# PS_Filter.net
KiCad netlist of a schematic drawn in Altium Designer
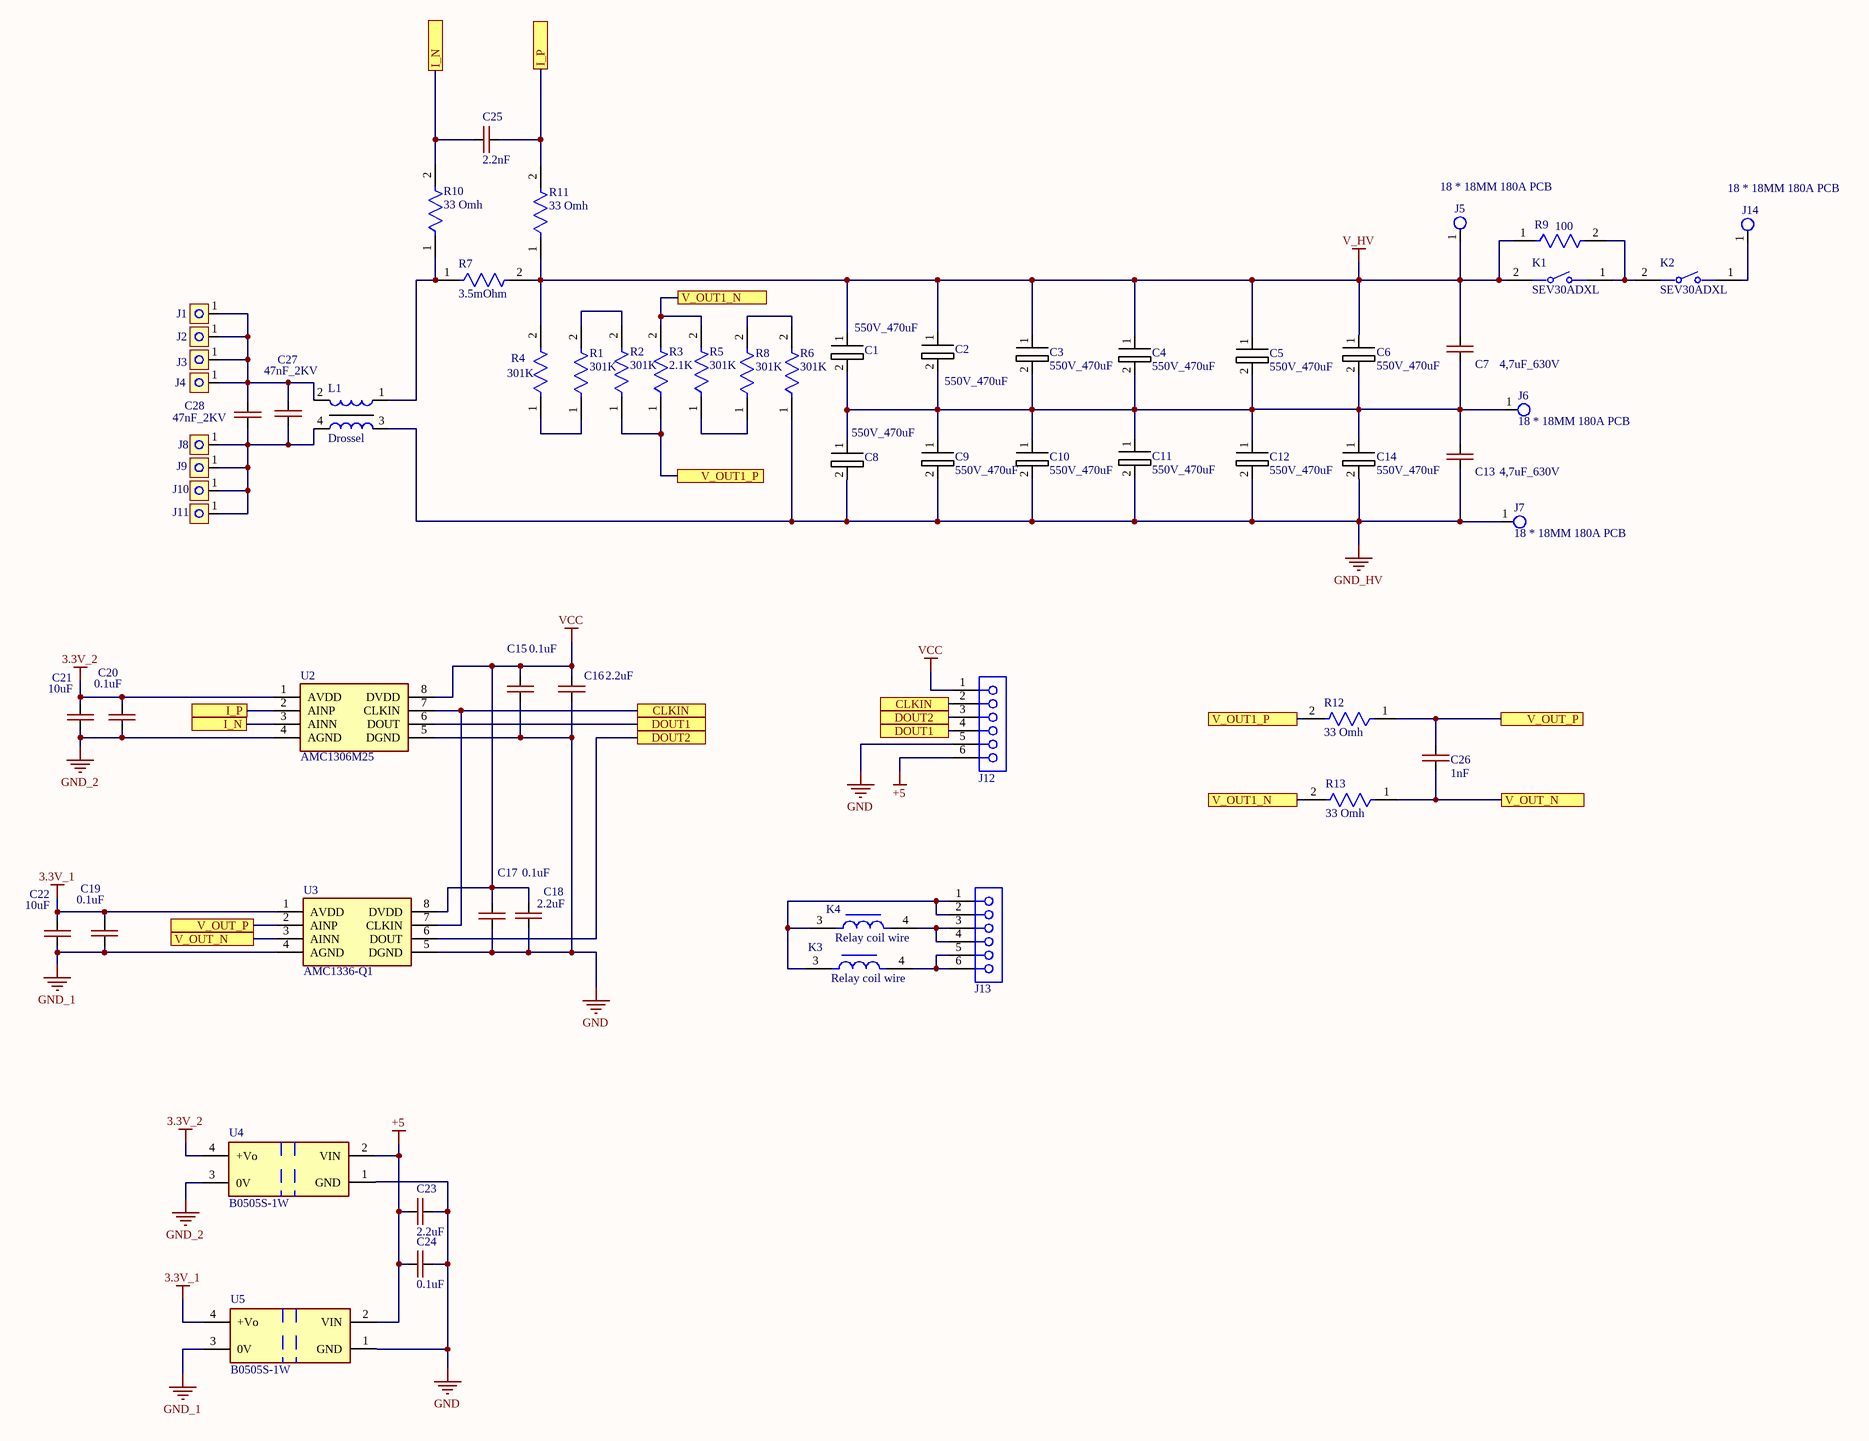
[diagram p0: PS_Filter.SchDoc]

(export (version "E")
  (design (tool "Eeschema 10.0.6"))
  (components
    (comp (ref "C1")
      (value "550V_470uF")
      (footprint "500V_470uF")
      (libsource (lib "PASSIVE_COMPONENTS") (part "CAP_POL_LOW_IMP"))
    )
    (comp (ref "C2")
      (value "550V_470uF")
      (footprint "500V_470uF")
      (libsource (lib "PASSIVE_COMPONENTS") (part "CAP_POL_LOW_IMP"))
    )
    (comp (ref "C3")
      (value "550V_470uF")
      (footprint "500V_470uF")
      (libsource (lib "PASSIVE_COMPONENTS") (part "CAP_POL_LOW_IMP"))
    )
    (comp (ref "C4")
      (value "550V_470uF")
      (footprint "500V_470uF")
      (libsource (lib "PASSIVE_COMPONENTS") (part "CAP_POL_LOW_IMP"))
    )
    (comp (ref "C5")
      (value "550V_470uF")
      (footprint "500V_470uF")
      (libsource (lib "PASSIVE_COMPONENTS") (part "CAP_POL_LOW_IMP"))
    )
    (comp (ref "C6")
      (value "550V_470uF")
      (footprint "500V_470uF")
      (libsource (lib "PASSIVE_COMPONENTS") (part "CAP_POL_LOW_IMP"))
    )
    (comp (ref "C7")
      (value "4,7uF_630V")
      (footprint "CAP_4.7uF_630V")
      (libsource (lib "PASSIVE_COMPONENTS") (part "CAP-NON-POLAR"))
    )
    (comp (ref "C8")
      (value "550V_470uF")
      (footprint "500V_470uF")
      (libsource (lib "PASSIVE_COMPONENTS") (part "CAP_POL_LOW_IMP"))
    )
    (comp (ref "C9")
      (value "550V_470uF")
      (footprint "500V_470uF")
      (libsource (lib "PASSIVE_COMPONENTS") (part "CAP_POL_LOW_IMP"))
    )
    (comp (ref "C10")
      (value "550V_470uF")
      (footprint "500V_470uF")
      (libsource (lib "PASSIVE_COMPONENTS") (part "CAP_POL_LOW_IMP"))
    )
    (comp (ref "C11")
      (value "550V_470uF")
      (footprint "500V_470uF")
      (libsource (lib "PASSIVE_COMPONENTS") (part "CAP_POL_LOW_IMP"))
    )
    (comp (ref "C12")
      (value "550V_470uF")
      (footprint "500V_470uF")
      (libsource (lib "PASSIVE_COMPONENTS") (part "CAP_POL_LOW_IMP"))
    )
    (comp (ref "C13")
      (value "4,7uF_630V")
      (footprint "CAP_4.7uF_630V")
      (libsource (lib "PASSIVE_COMPONENTS") (part "CAP-NON-POLAR"))
    )
    (comp (ref "C14")
      (value "550V_470uF")
      (footprint "500V_470uF")
      (libsource (lib "PASSIVE_COMPONENTS") (part "CAP_POL_LOW_IMP"))
    )
    (comp (ref "C15")
      (value "0.1uF")
      (footprint "CAP-0603")
      (libsource (lib "PASSIVE_COMPONENTS") (part "CAP-NON-POLAR"))
    )
    (comp (ref "C16")
      (value "2.2uF")
      (footprint "CAP-0603")
      (libsource (lib "PASSIVE_COMPONENTS") (part "CAP-NON-POLAR"))
    )
    (comp (ref "C17")
      (value "0.1uF")
      (footprint "CAP-0603")
      (libsource (lib "PASSIVE_COMPONENTS") (part "CAP-NON-POLAR"))
    )
    (comp (ref "C18")
      (value "2.2uF")
      (footprint "CAP-0603")
      (libsource (lib "PASSIVE_COMPONENTS") (part "CAP-NON-POLAR"))
    )
    (comp (ref "C19")
      (value "0.1uF")
      (footprint "CAP-0603")
      (libsource (lib "PASSIVE_COMPONENTS") (part "CAP-NON-POLAR"))
    )
    (comp (ref "C20")
      (value "0.1uF")
      (footprint "CAP-0603")
      (libsource (lib "PASSIVE_COMPONENTS") (part "CAP-NON-POLAR"))
    )
    (comp (ref "C21")
      (value "10uF")
      (footprint "CAP-0603")
      (libsource (lib "PASSIVE_COMPONENTS") (part "CAP-NON-POLAR"))
    )
    (comp (ref "C22")
      (value "10uF")
      (footprint "CAP-0603")
      (libsource (lib "PASSIVE_COMPONENTS") (part "CAP-NON-POLAR"))
    )
    (comp (ref "C23")
      (value "2.2uF")
      (footprint "CAP-0603")
      (libsource (lib "PASSIVE_COMPONENTS") (part "CAP-NON-POLAR"))
    )
    (comp (ref "C24")
      (value "0.1uF")
      (footprint "CAP-0603")
      (libsource (lib "PASSIVE_COMPONENTS") (part "CAP-NON-POLAR"))
    )
    (comp (ref "C25")
      (value "2.2nF")
      (footprint "CAP-0603")
      (libsource (lib "PASSIVE_COMPONENTS") (part "CAP-NON-POLAR"))
    )
    (comp (ref "C26")
      (value "1nF")
      (footprint "CAP-0603")
      (libsource (lib "PASSIVE_COMPONENTS") (part "CAP-NON-POLAR"))
    )
    (comp (ref "C27")
      (value "47nF_2KV")
      (footprint "47nF_2kV")
      (libsource (lib "PASSIVE_COMPONENTS") (part "CAP-V"))
    )
    (comp (ref "C28")
      (value "47nF_2KV")
      (footprint "47nF_2kV")
      (libsource (lib "PASSIVE_COMPONENTS") (part "CAP-V"))
    )
    (comp (ref "J1")
      (value "KF136HT-10.16")
      (footprint "Conn_MEIGAN_MG136HT")
      (libsource (lib "Connectors") (part "Connector_MEIGAN_MG136HT"))
    )
    (comp (ref "J2")
      (value "KF136HT-10.16")
      (footprint "Conn_MEIGAN_MG136HT")
      (libsource (lib "Connectors") (part "Connector_MEIGAN_MG136HT"))
    )
    (comp (ref "J3")
      (value "KF136HT-10.16")
      (footprint "Conn_MEIGAN_MG136HT")
      (libsource (lib "Connectors") (part "Connector_MEIGAN_MG136HT"))
    )
    (comp (ref "J4")
      (value "KF136HT-10.16")
      (footprint "Conn_MEIGAN_MG136HT")
      (libsource (lib "Connectors") (part "Connector_MEIGAN_MG136HT"))
    )
    (comp (ref "J5")
      (value "18 * 18MM 180A PCB")
      (footprint "M8 Conn")
      (description "18 * 18MM 180A PCB High Current Solder Terminal Copper Terminal Fastener M8 Nut")
      (libsource (lib "Connectors") (part "Klema_15_A"))
    )
    (comp (ref "J6")
      (value "18 * 18MM 180A PCB")
      (footprint "M8 Conn")
      (description "18 * 18MM 180A PCB High Current Solder Terminal Copper Terminal Fastener M8 Nut")
      (libsource (lib "Connectors") (part "Klema_15_A"))
    )
    (comp (ref "J7")
      (value "18 * 18MM 180A PCB")
      (footprint "M8 Conn")
      (description "18 * 18MM 180A PCB High Current Solder Terminal Copper Terminal Fastener M8 Nut")
      (libsource (lib "Connectors") (part "Klema_15_A"))
    )
    (comp (ref "J8")
      (value "KF136HT-10.16")
      (footprint "Conn_MEIGAN_MG136HT")
      (libsource (lib "Connectors") (part "Connector_MEIGAN_MG136HT"))
    )
    (comp (ref "J9")
      (value "KF136HT-10.16")
      (footprint "Conn_MEIGAN_MG136HT")
      (libsource (lib "Connectors") (part "Connector_MEIGAN_MG136HT"))
    )
    (comp (ref "J10")
      (value "KF136HT-10.16")
      (footprint "Conn_MEIGAN_MG136HT")
      (libsource (lib "Connectors") (part "Connector_MEIGAN_MG136HT"))
    )
    (comp (ref "J11")
      (value "KF136HT-10.16")
      (footprint "Conn_MEIGAN_MG136HT")
      (libsource (lib "Connectors") (part "Connector_MEIGAN_MG136HT"))
    )
    (comp (ref "J12")
      (value "61300611821")
      (footprint "61300611821")
      (description "WR-PHD Socket Header, THT, Vertical, pitch 2.54mm, 1 Row, 6P")
      (fields (field (name "MANUFACTURER") "Wurth Elektronik"))
      (libsource (lib "Altium_WR-PHD (rev24a)") (part "61300611821"))
    )
    (comp (ref "J13")
      (value "61300611821")
      (footprint "61300611821")
      (description "WR-PHD Socket Header, THT, Vertical, pitch 2.54mm, 1 Row, 6P")
      (fields (field (name "MANUFACTURER") "Wurth Elektronik"))
      (libsource (lib "Altium_WR-PHD (rev24a)") (part "61300611821"))
    )
    (comp (ref "J14")
      (value "18 * 18MM 180A PCB")
      (footprint "M8 Conn")
      (description "18 * 18MM 180A PCB High Current Solder Terminal Copper Terminal Fastener M8 Nut")
      (libsource (lib "Connectors") (part "Klema_15_A"))
    )
    (comp (ref "K1")
      (value "SEV30ADXL")
      (footprint "Relay_1000VDC_30A")
      (description "5-1000V 30A DC Contactor Power Relay SEV30ADXL Coil 12V")
      (libsource (lib "Relays") (part "Relay"))
    )
    (comp (ref "K2")
      (value "SEV30ADXL")
      (footprint "Relay_1000VDC_30A")
      (description "5-1000V 30A DC Contactor Power Relay SEV30ADXL Coil 12V")
      (libsource (lib "Relays") (part "Relay"))
    )
    (comp (ref "K3")
      (value "Relay coil wire")
      (footprint "Relay_Coil")
      (libsource (lib "Relays") (part "Coil_relay"))
    )
    (comp (ref "K4")
      (value "Relay coil wire")
      (footprint "Relay_Coil")
      (libsource (lib "Relays") (part "Coil_relay"))
    )
    (comp (ref "L1")
      (value "Drossel")
      (footprint "T47x27x15")
      (libsource (lib "Transformers") (part "Drossel_Synphaze"))
    )
    (comp (ref "R1")
      (value "301K")
      (footprint "RES-2512")
      (description "301K   0.1%")
      (libsource (lib "PASSIVE_COMPONENTS") (part "RES-CONST"))
    )
    (comp (ref "R2")
      (value "301K")
      (footprint "RES-2512")
      (description "301K   0.1%")
      (libsource (lib "PASSIVE_COMPONENTS") (part "RES-CONST"))
    )
    (comp (ref "R3")
      (value "2.1K")
      (footprint "RES-2512")
      (description "2.1K   0.1%")
      (libsource (lib "PASSIVE_COMPONENTS") (part "RES-CONST"))
    )
    (comp (ref "R4")
      (value "301K")
      (footprint "RES-2512")
      (description "301K   0.1%")
      (libsource (lib "PASSIVE_COMPONENTS") (part "RES-CONST"))
    )
    (comp (ref "R5")
      (value "301K")
      (footprint "RES-2512")
      (description "301K   0.1%")
      (libsource (lib "PASSIVE_COMPONENTS") (part "RES-CONST"))
    )
    (comp (ref "R6")
      (value "301K")
      (footprint "RES-2512")
      (description "301K   0.1%")
      (libsource (lib "PASSIVE_COMPONENTS") (part "RES-CONST"))
    )
    (comp (ref "R7")
      (value "3.5mOhm")
      (footprint "RES-3921")
      (description "3.5mOhm 1%  3920")
      (libsource (lib "PASSIVE_COMPONENTS") (part "RES-CONST"))
    )
    (comp (ref "R8")
      (value "301K")
      (footprint "RES-2512")
      (description "301K   0.1%")
      (libsource (lib "PASSIVE_COMPONENTS") (part "RES-CONST"))
    )
    (comp (ref "R9")
      (value "100")
      (footprint "RES_100W_Aluminium")
      (description "100W RX24 Aluminum Power Metal Shell Case Wirewound Resistor 100Omh")
      (libsource (lib "PASSIVE_COMPONENTS") (part "RES-CONST"))
    )
    (comp (ref "R10")
      (value "33 Omh")
      (footprint "RES-0603")
      (libsource (lib "PASSIVE_COMPONENTS") (part "RES-CONST"))
    )
    (comp (ref "R11")
      (value "33 Omh")
      (footprint "RES-0603")
      (libsource (lib "PASSIVE_COMPONENTS") (part "RES-CONST"))
    )
    (comp (ref "R12")
      (value "33 Omh")
      (footprint "RES-0603")
      (libsource (lib "PASSIVE_COMPONENTS") (part "RES-CONST"))
    )
    (comp (ref "R13")
      (value "33 Omh")
      (footprint "RES-0603")
      (libsource (lib "PASSIVE_COMPONENTS") (part "RES-CONST"))
    )
    (comp (ref "U2")
      (value "AMC1306M25")
      (footprint "FP-DWV0008A-MFG")
      (libsource (lib "Integrated_Circuts") (part "AMC1306M25"))
    )
    (comp (ref "U3")
      (value "AMC1336-Q1")
      (footprint "FP-DWV0008A-MFG")
      (libsource (lib "Integrated_Circuts") (part "AMC1336"))
    )
    (comp (ref "U4")
      (value "B0505S-1W")
      (footprint "B0505S-1W")
      (libsource (lib "Integrated_Circuts") (part "B0505S-1W"))
    )
    (comp (ref "U5")
      (value "B0505S-1W")
      (footprint "B0505S-1W")
      (libsource (lib "Integrated_Circuts") (part "B0505S-1W"))
    )
  )
  (nets
    (net (code "1") (name "+5") (class "Default")
      (node (ref "C23") (pin "1") (pinfunction "1_1") (pintype "passive"))
      (node (ref "C24") (pin "1") (pinfunction "1_1") (pintype "passive"))
      (node (ref "J12") (pin "6") (pinfunction "6_6") (pintype "passive"))
      (node (ref "U4") (pin "2") (pinfunction "VIN_2") (pintype "power_in"))
      (node (ref "U5") (pin "2") (pinfunction "VIN_2") (pintype "power_in"))
    )
    (net (code "2") (name "/CLKIN") (class "Default")
      (node (ref "J12") (pin "2") (pinfunction "2_2") (pintype "passive"))
      (node (ref "U2") (pin "7") (pinfunction "CLKIN_7") (pintype "passive"))
      (node (ref "U3") (pin "7") (pinfunction "CLKIN_7") (pintype "passive"))
    )
    (net (code "3") (name "/DOUT1") (class "Default")
      (node (ref "J12") (pin "4") (pinfunction "4_4") (pintype "passive"))
      (node (ref "U2") (pin "6") (pinfunction "DOUT_6") (pintype "passive"))
    )
    (net (code "4") (name "/DOUT2") (class "Default")
      (node (ref "J12") (pin "3") (pinfunction "3_3") (pintype "passive"))
      (node (ref "U3") (pin "6") (pinfunction "DOUT_6") (pintype "passive"))
    )
    (net (code "5") (name "/I_N") (class "Default")
      (node (ref "C25") (pin "1") (pinfunction "1_1") (pintype "passive"))
      (node (ref "R10") (pin "2") (pinfunction "2_2") (pintype "passive"))
      (node (ref "U2") (pin "3") (pinfunction "AINN_3") (pintype "passive"))
    )
    (net (code "6") (name "/I_P") (class "Default")
      (node (ref "C25") (pin "2") (pinfunction "2_2") (pintype "passive"))
      (node (ref "R11") (pin "2") (pinfunction "2_2") (pintype "passive"))
      (node (ref "U2") (pin "2") (pinfunction "AINP_2") (pintype "passive"))
    )
    (net (code "7") (name "/V_OUT1_N") (class "Default")
      (node (ref "R13") (pin "2") (pinfunction "2_2") (pintype "passive"))
      (node (ref "R3") (pin "2") (pinfunction "2_2") (pintype "passive"))
      (node (ref "R5") (pin "2") (pinfunction "2_2") (pintype "passive"))
    )
    (net (code "8") (name "/V_OUT1_P") (class "Default")
      (node (ref "R12") (pin "2") (pinfunction "2_2") (pintype "passive"))
      (node (ref "R2") (pin "1") (pinfunction "1_1") (pintype "passive"))
      (node (ref "R3") (pin "1") (pinfunction "1_1") (pintype "passive"))
    )
    (net (code "9") (name "/V_OUT_N") (class "Default")
      (node (ref "C26") (pin "2") (pinfunction "2_2") (pintype "passive"))
      (node (ref "R13") (pin "1") (pinfunction "1_1") (pintype "passive"))
      (node (ref "U3") (pin "3") (pinfunction "AINN_3") (pintype "passive"))
    )
    (net (code "10") (name "/V_OUT_P") (class "Default")
      (node (ref "C26") (pin "1") (pinfunction "1_1") (pintype "passive"))
      (node (ref "R12") (pin "1") (pinfunction "1_1") (pintype "passive"))
      (node (ref "U3") (pin "2") (pinfunction "AINP_2") (pintype "passive"))
    )
    (net (code "11") (name "3.3V_1") (class "Default")
      (node (ref "C19") (pin "1") (pinfunction "1_1") (pintype "passive"))
      (node (ref "C22") (pin "1") (pinfunction "1_1") (pintype "passive"))
      (node (ref "U3") (pin "1") (pinfunction "AVDD_1") (pintype "passive"))
      (node (ref "U5") (pin "4") (pinfunction "+Vo_4") (pintype "power_in"))
    )
    (net (code "12") (name "3.3V_2") (class "Default")
      (node (ref "C20") (pin "1") (pinfunction "1_1") (pintype "passive"))
      (node (ref "C21") (pin "1") (pinfunction "1_1") (pintype "passive"))
      (node (ref "U2") (pin "1") (pinfunction "AVDD_1") (pintype "passive"))
      (node (ref "U4") (pin "4") (pinfunction "+Vo_4") (pintype "power_in"))
    )
    (net (code "13") (name "GND") (class "Default")
      (node (ref "C15") (pin "2") (pinfunction "2_2") (pintype "passive"))
      (node (ref "C16") (pin "2") (pinfunction "2_2") (pintype "passive"))
      (node (ref "C17") (pin "2") (pinfunction "2_2") (pintype "passive"))
      (node (ref "C18") (pin "2") (pinfunction "2_2") (pintype "passive"))
      (node (ref "C23") (pin "2") (pinfunction "2_2") (pintype "passive"))
      (node (ref "C24") (pin "2") (pinfunction "2_2") (pintype "passive"))
      (node (ref "J12") (pin "5") (pinfunction "5_5") (pintype "passive"))
      (node (ref "U2") (pin "5") (pinfunction "DGND_5") (pintype "passive"))
      (node (ref "U3") (pin "5") (pinfunction "DGND_5") (pintype "passive"))
      (node (ref "U4") (pin "1") (pinfunction "GND_1") (pintype "power_in"))
      (node (ref "U5") (pin "1") (pinfunction "GND_1") (pintype "power_in"))
    )
    (net (code "14") (name "GND_1") (class "Default")
      (node (ref "C19") (pin "2") (pinfunction "2_2") (pintype "passive"))
      (node (ref "C22") (pin "2") (pinfunction "2_2") (pintype "passive"))
      (node (ref "U3") (pin "4") (pinfunction "AGND_4") (pintype "passive"))
      (node (ref "U5") (pin "3") (pinfunction "0V_3") (pintype "power_in"))
    )
    (net (code "15") (name "GND_2") (class "Default")
      (node (ref "C20") (pin "2") (pinfunction "2_2") (pintype "passive"))
      (node (ref "C21") (pin "2") (pinfunction "2_2") (pintype "passive"))
      (node (ref "U2") (pin "4") (pinfunction "AGND_4") (pintype "passive"))
      (node (ref "U4") (pin "3") (pinfunction "0V_3") (pintype "power_in"))
    )
    (net (code "16") (name "GND_HV") (class "Default")
      (node (ref "C10") (pin "2") (pinfunction "2_2") (pintype "passive"))
      (node (ref "C11") (pin "2") (pinfunction "2_2") (pintype "passive"))
      (node (ref "C12") (pin "2") (pinfunction "2_2") (pintype "passive"))
      (node (ref "C13") (pin "1") (pinfunction "1_1") (pintype "passive"))
      (node (ref "C14") (pin "2") (pinfunction "2_2") (pintype "passive"))
      (node (ref "C8") (pin "2") (pinfunction "2_2") (pintype "passive"))
      (node (ref "C9") (pin "2") (pinfunction "2_2") (pintype "passive"))
      (node (ref "J7") (pin "1") (pinfunction "0_1") (pintype "passive"))
      (node (ref "L1") (pin "3") (pinfunction "3_3") (pintype "passive"))
      (node (ref "R6") (pin "1") (pinfunction "1_1") (pintype "passive"))
    )
    (net (code "17") (name "Net-(J1-17)") (class "Default")
      (node (ref "C27") (pin "2") (pinfunction "2_2") (pintype "passive"))
      (node (ref "C28") (pin "2") (pinfunction "2_2") (pintype "passive"))
      (node (ref "J1") (pin "1") (pinfunction "17_1") (pintype "passive"))
      (node (ref "J2") (pin "1") (pinfunction "17_1") (pintype "passive"))
      (node (ref "J3") (pin "1") (pinfunction "17_1") (pintype "passive"))
      (node (ref "J4") (pin "1") (pinfunction "17_1") (pintype "passive"))
      (node (ref "L1") (pin "2") (pinfunction "2_2") (pintype "passive"))
    )
    (net (code "18") (name "Net-(J6-0)") (class "Default")
      (node (ref "C1") (pin "2") (pinfunction "2_2") (pintype "passive"))
      (node (ref "C10") (pin "1") (pinfunction "1_1") (pintype "passive"))
      (node (ref "C11") (pin "1") (pinfunction "1_1") (pintype "passive"))
      (node (ref "C12") (pin "1") (pinfunction "1_1") (pintype "passive"))
      (node (ref "C13") (pin "2") (pinfunction "2_2") (pintype "passive"))
      (node (ref "C14") (pin "1") (pinfunction "1_1") (pintype "passive"))
      (node (ref "C2") (pin "2") (pinfunction "2_2") (pintype "passive"))
      (node (ref "C3") (pin "2") (pinfunction "2_2") (pintype "passive"))
      (node (ref "C4") (pin "2") (pinfunction "2_2") (pintype "passive"))
      (node (ref "C5") (pin "2") (pinfunction "2_2") (pintype "passive"))
      (node (ref "C6") (pin "2") (pinfunction "2_2") (pintype "passive"))
      (node (ref "C7") (pin "1") (pinfunction "1_1") (pintype "passive"))
      (node (ref "C8") (pin "1") (pinfunction "1_1") (pintype "passive"))
      (node (ref "C9") (pin "1") (pinfunction "1_1") (pintype "passive"))
      (node (ref "J6") (pin "1") (pinfunction "0_1") (pintype "passive"))
    )
    (net (code "19") (name "Net-(J10-17)") (class "Default")
      (node (ref "C27") (pin "1") (pinfunction "1_1") (pintype "passive"))
      (node (ref "C28") (pin "1") (pinfunction "1_1") (pintype "passive"))
      (node (ref "J10") (pin "1") (pinfunction "17_1") (pintype "passive"))
      (node (ref "J11") (pin "1") (pinfunction "17_1") (pintype "passive"))
      (node (ref "J8") (pin "1") (pinfunction "17_1") (pintype "passive"))
      (node (ref "J9") (pin "1") (pinfunction "17_1") (pintype "passive"))
      (node (ref "L1") (pin "4") (pinfunction "4_4") (pintype "passive"))
    )
    (net (code "20") (name "Net-(J13-Pad1)") (class "Default")
      (node (ref "J13") (pin "1") (pinfunction "1_1") (pintype "passive"))
      (node (ref "J13") (pin "2") (pinfunction "2_2") (pintype "passive"))
      (node (ref "K3") (pin "3") (pinfunction "3_3") (pintype "passive"))
      (node (ref "K4") (pin "3") (pinfunction "3_3") (pintype "passive"))
    )
    (net (code "21") (name "Net-(J13-Pad3)") (class "Default")
      (node (ref "J13") (pin "3") (pinfunction "3_3") (pintype "passive"))
      (node (ref "J13") (pin "4") (pinfunction "4_4") (pintype "passive"))
      (node (ref "K4") (pin "4") (pinfunction "4_4") (pintype "passive"))
    )
    (net (code "22") (name "Net-(J13-Pad5)") (class "Default")
      (node (ref "J13") (pin "5") (pinfunction "5_5") (pintype "passive"))
      (node (ref "J13") (pin "6") (pinfunction "6_6") (pintype "passive"))
      (node (ref "K3") (pin "4") (pinfunction "4_4") (pintype "passive"))
    )
    (net (code "23") (name "Net-(J14-0)") (class "Default")
      (node (ref "J14") (pin "1") (pinfunction "0_1") (pintype "passive"))
      (node (ref "K2") (pin "1") (pinfunction "1_1") (pintype "passive"))
    )
    (net (code "24") (name "Net-(K1-Pad1)") (class "Default")
      (node (ref "K1") (pin "1") (pinfunction "1_1") (pintype "passive"))
      (node (ref "K2") (pin "2") (pinfunction "2_2") (pintype "passive"))
      (node (ref "R9") (pin "2") (pinfunction "2_2") (pintype "passive"))
    )
    (net (code "25") (name "Net-(L1-Pad1)") (class "Default")
      (node (ref "L1") (pin "1") (pinfunction "1_1") (pintype "passive"))
      (node (ref "R10") (pin "1") (pinfunction "1_1") (pintype "passive"))
      (node (ref "R7") (pin "1") (pinfunction "1_1") (pintype "passive"))
    )
    (net (code "26") (name "Net-(R1-Pad1)") (class "Default")
      (node (ref "R1") (pin "1") (pinfunction "1_1") (pintype "passive"))
      (node (ref "R4") (pin "1") (pinfunction "1_1") (pintype "passive"))
    )
    (net (code "27") (name "Net-(R1-Pad2)") (class "Default")
      (node (ref "R1") (pin "2") (pinfunction "2_2") (pintype "passive"))
      (node (ref "R2") (pin "2") (pinfunction "2_2") (pintype "passive"))
    )
    (net (code "28") (name "Net-(R5-Pad1)") (class "Default")
      (node (ref "R5") (pin "1") (pinfunction "1_1") (pintype "passive"))
      (node (ref "R8") (pin "1") (pinfunction "1_1") (pintype "passive"))
    )
    (net (code "29") (name "Net-(R6-Pad2)") (class "Default")
      (node (ref "R6") (pin "2") (pinfunction "2_2") (pintype "passive"))
      (node (ref "R8") (pin "2") (pinfunction "2_2") (pintype "passive"))
    )
    (net (code "30") (name "VCC") (class "Default")
      (node (ref "C15") (pin "1") (pinfunction "1_1") (pintype "passive"))
      (node (ref "C16") (pin "1") (pinfunction "1_1") (pintype "passive"))
      (node (ref "C17") (pin "1") (pinfunction "1_1") (pintype "passive"))
      (node (ref "C18") (pin "1") (pinfunction "1_1") (pintype "passive"))
      (node (ref "J12") (pin "1") (pinfunction "1_1") (pintype "passive"))
      (node (ref "U2") (pin "8") (pinfunction "DVDD_8") (pintype "passive"))
      (node (ref "U3") (pin "8") (pinfunction "DVDD_8") (pintype "passive"))
    )
    (net (code "31") (name "V_HV") (class "Default")
      (node (ref "C1") (pin "1") (pinfunction "1_1") (pintype "passive"))
      (node (ref "C2") (pin "1") (pinfunction "1_1") (pintype "passive"))
      (node (ref "C3") (pin "1") (pinfunction "1_1") (pintype "passive"))
      (node (ref "C4") (pin "1") (pinfunction "1_1") (pintype "passive"))
      (node (ref "C5") (pin "1") (pinfunction "1_1") (pintype "passive"))
      (node (ref "C6") (pin "1") (pinfunction "1_1") (pintype "passive"))
      (node (ref "C7") (pin "2") (pinfunction "2_2") (pintype "passive"))
      (node (ref "J5") (pin "1") (pinfunction "0_1") (pintype "passive"))
      (node (ref "K1") (pin "2") (pinfunction "2_2") (pintype "passive"))
      (node (ref "R11") (pin "1") (pinfunction "1_1") (pintype "passive"))
      (node (ref "R4") (pin "2") (pinfunction "2_2") (pintype "passive"))
      (node (ref "R7") (pin "2") (pinfunction "2_2") (pintype "passive"))
      (node (ref "R9") (pin "1") (pinfunction "1_1") (pintype "passive"))
    )
  )
)
